# THS7002CPWP_Schematic.net
KiCad netlist of a schematic drawn in Altium Designer
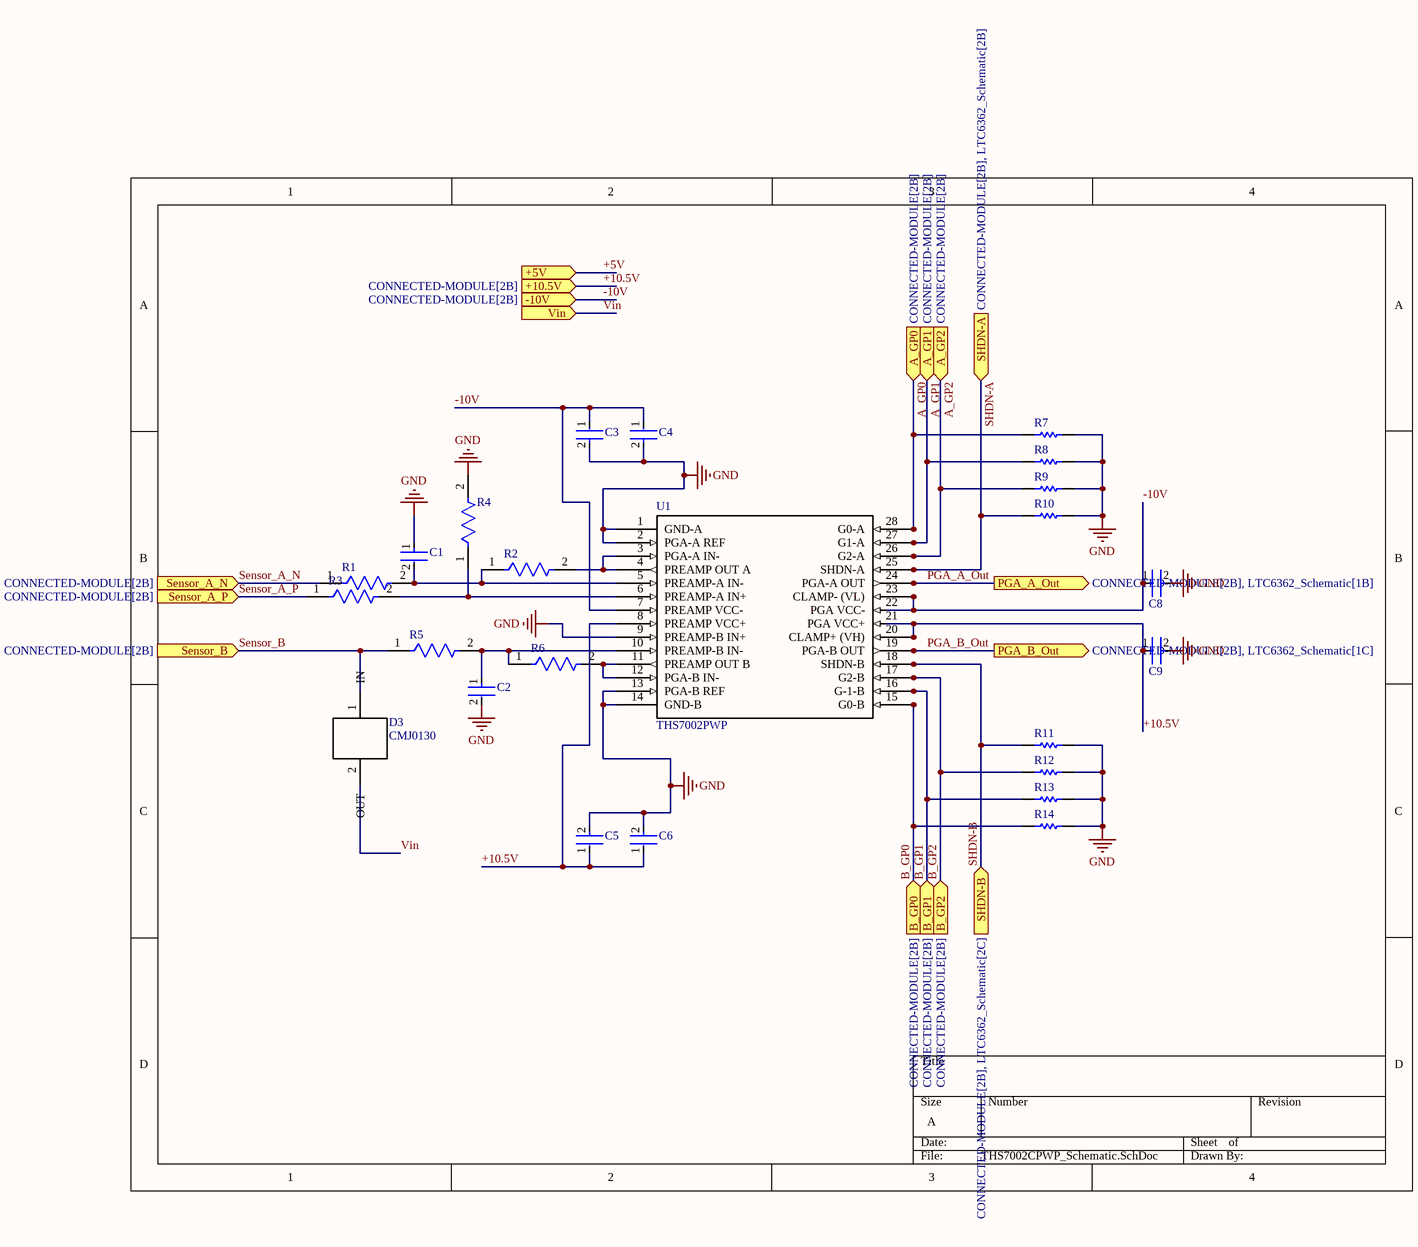
[diagram p0: THS7002CPWP_Schematic.SchDoc]

(export (version "E")
  (design (tool "Eeschema 10.0.6"))
  (components
    (comp (ref "C1")
      (value "GRM1557U1A302JA01D")
      (footprint "FP-GRM155-0_05-IPC_B")
      (description "Chip Multilayer Ceramic Capacitors for General Purpose, 0402, 3000pF, U2J, -750ppm/°C, 5%, 10V")
      (fields (field (name "TOLERANCE") "5%"))
      (libsource (lib "Altium Content Vault") (part "02cd4be3c70576c341d710602a673aa"))
    )
    (comp (ref "C2")
      (value "C0603C622J5GACTU")
      (footprint "FP-C0603C-CF-MFG")
      (fields
        (field (name "MANUFACTURER") "KEMET")
        (field (name "OCTOPART") "https://octopart.com/c0603c622j5gactu-kemet-19757383")
        (field (name "TOLERANCE") "0.05")
      )
      (libsource (lib "Altium Content Vault") (part "b4654b650e69147ec39a6b967a45e02"))
    )
    (comp (ref "C3")
      (value "GRM155R71C104KA88D")
      (footprint "FP-GRM15-MFG")
      (description "CAP CER 0.1UF 16V X7R 0402")
      (fields
        (field (name "TOLERANCE") "10%")
        (field (name "OCTOPART") "https://octopart.com/grm155r71c104ka88d-murata-196880")
      )
      (libsource (lib "Altium Content Vault") (part "236180d848d6139a670b325ea6854c9"))
    )
    (comp (ref "C4")
      (value "C1608X5R1A685K080AC")
      (footprint "FP-C1608-080-0_1-IPC_B")
      (description "Multilayer Ceramic Capacitors 6.8μF ±10% 10V X5R SMD 0603")
      (fields (field (name "TOLERANCE") "10%"))
      (libsource (lib "Altium Content Vault") (part "236180d848d6139a670b325ea6854c9"))
    )
    (comp (ref "C5")
      (value "GRM155R71C104KA88D")
      (footprint "FP-GRM15-MFG")
      (description "CAP CER 0.1UF 16V X7R 0402")
      (fields
        (field (name "TOLERANCE") "10%")
        (field (name "OCTOPART") "https://octopart.com/grm155r71c104ka88d-murata-196880")
      )
      (libsource (lib "Altium Content Vault") (part "236180d848d6139a670b325ea6854c9"))
    )
    (comp (ref "C6")
      (value "C1608X5R1A685K080AC")
      (footprint "FP-C1608-080-0_1-IPC_B")
      (description "Multilayer Ceramic Capacitors 6.8μF ±10% 10V X5R SMD 0603")
      (fields (field (name "TOLERANCE") "10%"))
      (libsource (lib "Altium Content Vault") (part "236180d848d6139a670b325ea6854c9"))
    )
    (comp (ref "C8")
      (value "GRM155R71C104KA88D")
      (footprint "FP-GRM15-MFG")
      (description "CAP CER 0.1UF 16V X7R 0402")
      (fields
        (field (name "TOLERANCE") "10%")
        (field (name "OCTOPART") "https://octopart.com/grm155r71c104ka88d-murata-196880")
      )
      (libsource (lib "Altium Content Vault") (part "236180d848d6139a670b325ea6854c9"))
    )
    (comp (ref "C9")
      (value "GRM155R71C104KA88D")
      (footprint "FP-GRM15-MFG")
      (description "CAP CER 0.1UF 16V X7R 0402")
      (fields
        (field (name "TOLERANCE") "10%")
        (field (name "OCTOPART") "https://octopart.com/grm155r71c104ka88d-murata-196880")
      )
      (libsource (lib "Altium Content Vault") (part "236180d848d6139a670b325ea6854c9"))
    )
    (comp (ref "D3")
      (value "CMJ0130")
      (footprint "CMJ2000_Footprint")
      (description "CMJ2000: DIODE CUR REG 100V 2.32MA 500MW; CMJ0130 DIODE CUR REG 100V 0.5mA 500MW")
      (libsource (lib "CMJ2000_Schematic") (part "CMJ2000/0130"))
    )
    (comp (ref "R1")
      (value "CRCW0402499RFKED")
      (footprint "FP-CRCW0402-e3-IPC_A")
      (description "RES Thick Film, 499Ω, 1%, 0.063W, 100ppm/°C, 0402")
      (fields (field (name "TOLERANCE") "1%"))
      (libsource (lib "Altium Content Vault") (part "1029c3af85768c4190bb7ad29bc67b5"))
    )
    (comp (ref "R2")
      (value "CRCW0402499RFKED")
      (footprint "FP-CRCW0402-e3-IPC_A")
      (description "RES Thick Film, 499Ω, 1%, 0.063W, 100ppm/°C, 0402")
      (fields (field (name "TOLERANCE") "1%"))
      (libsource (lib "Altium Content Vault") (part "1029c3af85768c4190bb7ad29bc67b5"))
    )
    (comp (ref "R3")
      (value "CRCW0402499RFKED")
      (footprint "FP-CRCW0402-e3-IPC_A")
      (description "RES Thick Film, 499Ω, 1%, 0.063W, 100ppm/°C, 0402")
      (fields (field (name "TOLERANCE") "1%"))
      (libsource (lib "Altium Content Vault") (part "1029c3af85768c4190bb7ad29bc67b5"))
    )
    (comp (ref "R4")
      (value "CRCW0402499RFKED")
      (footprint "FP-CRCW0402-e3-IPC_A")
      (description "RES Thick Film, 499Ω, 1%, 0.063W, 100ppm/°C, 0402")
      (fields (field (name "TOLERANCE") "1%"))
      (libsource (lib "Altium Content Vault") (part "1029c3af85768c4190bb7ad29bc67b5"))
    )
    (comp (ref "R5")
      (value "CRCW0402499RFKED")
      (footprint "FP-CRCW0402-e3-IPC_A")
      (description "RES Thick Film, 499Ω, 1%, 0.063W, 100ppm/°C, 0402")
      (fields (field (name "TOLERANCE") "1%"))
      (libsource (lib "Altium Content Vault") (part "1029c3af85768c4190bb7ad29bc67b5"))
    )
    (comp (ref "R6")
      (value "CRCW0402499RFKED")
      (footprint "FP-CRCW0402-e3-IPC_A")
      (description "RES Thick Film, 499Ω, 1%, 0.063W, 100ppm/°C, 0402")
      (fields (field (name "TOLERANCE") "1%"))
      (libsource (lib "Altium Content Vault") (part "1029c3af85768c4190bb7ad29bc67b5"))
    )
    (comp (ref "R7")
      (value "ERJ-2RKF3301X")
      (footprint "RESC1005X40X25ML05T05")
      (description "Chip Resistor, 3.3 KOhm, +/- 1%, 0.1 W, -55 to 155 degC, 0402 (1005 Metric), RoHS, Tape and Reel")
      (fields (field (name "MANUFACTURER") "Panasonic") (field (name "TOLERANCE") "1%"))
      (libsource (lib "Altium Content Vault") (part "RES-2"))
    )
    (comp (ref "R8")
      (value "ERJ-2RKF3301X")
      (footprint "RESC1005X40X25ML05T05")
      (description "Chip Resistor, 3.3 KOhm, +/- 1%, 0.1 W, -55 to 155 degC, 0402 (1005 Metric), RoHS, Tape and Reel")
      (fields (field (name "MANUFACTURER") "Panasonic") (field (name "TOLERANCE") "1%"))
      (libsource (lib "Altium Content Vault") (part "RES-2"))
    )
    (comp (ref "R9")
      (value "ERJ-2RKF3301X")
      (footprint "RESC1005X40X25ML05T05")
      (description "Chip Resistor, 3.3 KOhm, +/- 1%, 0.1 W, -55 to 155 degC, 0402 (1005 Metric), RoHS, Tape and Reel")
      (fields (field (name "MANUFACTURER") "Panasonic") (field (name "TOLERANCE") "1%"))
      (libsource (lib "Altium Content Vault") (part "RES-2"))
    )
    (comp (ref "R10")
      (value "ERJ-2RKF3301X")
      (footprint "RESC1005X40X25ML05T05")
      (description "Chip Resistor, 3.3 KOhm, +/- 1%, 0.1 W, -55 to 155 degC, 0402 (1005 Metric), RoHS, Tape and Reel")
      (fields (field (name "MANUFACTURER") "Panasonic") (field (name "TOLERANCE") "1%"))
      (libsource (lib "Altium Content Vault") (part "RES-2"))
    )
    (comp (ref "R11")
      (value "ERJ-2RKF3301X")
      (footprint "RESC1005X40X25ML05T05")
      (description "Chip Resistor, 3.3 KOhm, +/- 1%, 0.1 W, -55 to 155 degC, 0402 (1005 Metric), RoHS, Tape and Reel")
      (fields (field (name "MANUFACTURER") "Panasonic") (field (name "TOLERANCE") "1%"))
      (libsource (lib "Altium Content Vault") (part "RES-2"))
    )
    (comp (ref "R12")
      (value "ERJ-2RKF3301X")
      (footprint "RESC1005X40X25ML05T05")
      (description "Chip Resistor, 3.3 KOhm, +/- 1%, 0.1 W, -55 to 155 degC, 0402 (1005 Metric), RoHS, Tape and Reel")
      (fields (field (name "MANUFACTURER") "Panasonic") (field (name "TOLERANCE") "1%"))
      (libsource (lib "Altium Content Vault") (part "RES-2"))
    )
    (comp (ref "R13")
      (value "ERJ-2RKF3301X")
      (footprint "RESC1005X40X25ML05T05")
      (description "Chip Resistor, 3.3 KOhm, +/- 1%, 0.1 W, -55 to 155 degC, 0402 (1005 Metric), RoHS, Tape and Reel")
      (fields (field (name "MANUFACTURER") "Panasonic") (field (name "TOLERANCE") "1%"))
      (libsource (lib "Altium Content Vault") (part "RES-2"))
    )
    (comp (ref "R14")
      (value "ERJ-2RKF3301X")
      (footprint "RESC1005X40X25ML05T05")
      (description "Chip Resistor, 3.3 KOhm, +/- 1%, 0.1 W, -55 to 155 degC, 0402 (1005 Metric), RoHS, Tape and Reel")
      (fields (field (name "MANUFACTURER") "Panasonic") (field (name "TOLERANCE") "1%"))
      (libsource (lib "Altium Content Vault") (part "RES-2"))
    )
    (comp (ref "U1")
      (value "THS7002PWP")
      (footprint "PWP0028E_N")
      (libsource (lib "THS7002_New_Schematic") (part "Component_1"))
    )
  )
  (nets
    (net (code "2") (name "/+10.5V") (class "Default")
      (node (ref "C5") (pin "1") (pinfunction "1_1") (pintype "passive"))
      (node (ref "C6") (pin "1") (pinfunction "1_1") (pintype "passive"))
      (node (ref "C9") (pin "1") (pinfunction "1_1") (pintype "passive"))
      (node (ref "U1") (pin "20") (pinfunction "CLAMP+_(VH)_20") (pintype "input"))
      (node (ref "U1") (pin "21") (pinfunction "PGA_VCC+_21") (pintype "input"))
      (node (ref "U1") (pin "8") (pinfunction "PREAMP_VCC+_8") (pintype "input"))
    )
    (net (code "3") (name "/-10V") (class "Default")
      (node (ref "C3") (pin "1") (pinfunction "1_1") (pintype "passive"))
      (node (ref "C4") (pin "1") (pinfunction "1_1") (pintype "passive"))
      (node (ref "C8") (pin "1") (pinfunction "1_1") (pintype "passive"))
      (node (ref "U1") (pin "22") (pinfunction "PGA_VCC-_22") (pintype "input"))
      (node (ref "U1") (pin "23") (pinfunction "CLAMP-_(VL)_23") (pintype "input"))
      (node (ref "U1") (pin "7") (pinfunction "PREAMP_VCC-_7") (pintype "input"))
    )
    (net (code "4") (name "/A_GP0") (class "Default")
      (node (ref "R7") (pin "1") (pinfunction "1_1") (pintype "passive"))
      (node (ref "U1") (pin "28") (pinfunction "G0-A_28") (pintype "input"))
    )
    (net (code "5") (name "/A_GP1") (class "Default")
      (node (ref "R8") (pin "1") (pinfunction "1_1") (pintype "passive"))
      (node (ref "U1") (pin "27") (pinfunction "G1-A_27") (pintype "input"))
    )
    (net (code "6") (name "/A_GP2") (class "Default")
      (node (ref "R9") (pin "1") (pinfunction "1_1") (pintype "passive"))
      (node (ref "U1") (pin "26") (pinfunction "G2-A_26") (pintype "input"))
    )
    (net (code "7") (name "/B_GP0") (class "Default")
      (node (ref "R14") (pin "1") (pinfunction "1_1") (pintype "passive"))
      (node (ref "U1") (pin "15") (pinfunction "G0-B_15") (pintype "input"))
    )
    (net (code "8") (name "/B_GP1") (class "Default")
      (node (ref "R13") (pin "1") (pinfunction "1_1") (pintype "passive"))
      (node (ref "U1") (pin "16") (pinfunction "G-1-B_16") (pintype "input"))
    )
    (net (code "9") (name "/B_GP2") (class "Default")
      (node (ref "R12") (pin "1") (pinfunction "1_1") (pintype "passive"))
      (node (ref "U1") (pin "17") (pinfunction "G2-B_17") (pintype "input"))
    )
    (net (code "10") (name "/PGA_A_Out") (class "Default")
      (node (ref "U1") (pin "24") (pinfunction "PGA-A_OUT_24") (pintype "output"))
    )
    (net (code "11") (name "/PGA_B_Out") (class "Default")
      (node (ref "U1") (pin "19") (pinfunction "PGA-B_OUT_19") (pintype "output"))
    )
    (net (code "12") (name "/SHDN-A") (class "Default")
      (node (ref "R10") (pin "1") (pinfunction "1_1") (pintype "passive"))
      (node (ref "U1") (pin "25") (pinfunction "SHDN-A_25") (pintype "input"))
    )
    (net (code "13") (name "/SHDN-B") (class "Default")
      (node (ref "R11") (pin "1") (pinfunction "1_1") (pintype "passive"))
      (node (ref "U1") (pin "18") (pinfunction "SHDN-B_18") (pintype "input"))
    )
    (net (code "14") (name "/Sensor_A_N") (class "Default")
      (node (ref "R1") (pin "1") (pinfunction "1_1") (pintype "passive"))
    )
    (net (code "15") (name "/Sensor_A_P") (class "Default")
      (node (ref "R3") (pin "1") (pinfunction "1_1") (pintype "passive"))
    )
    (net (code "16") (name "/Sensor_B") (class "Default")
      (node (ref "R5") (pin "1") (pinfunction "1_1") (pintype "passive"))
    )
    (net (code "18") (name "GND") (class "Default")
      (node (ref "C1") (pin "1") (pinfunction "1_1") (pintype "passive"))
      (node (ref "C2") (pin "2") (pinfunction "2_2") (pintype "passive"))
      (node (ref "C3") (pin "2") (pinfunction "2_2") (pintype "passive"))
      (node (ref "C4") (pin "2") (pinfunction "2_2") (pintype "passive"))
      (node (ref "C5") (pin "2") (pinfunction "2_2") (pintype "passive"))
      (node (ref "C6") (pin "2") (pinfunction "2_2") (pintype "passive"))
      (node (ref "C8") (pin "2") (pinfunction "2_2") (pintype "passive"))
      (node (ref "C9") (pin "2") (pinfunction "2_2") (pintype "passive"))
      (node (ref "R10") (pin "2") (pinfunction "2_2") (pintype "passive"))
      (node (ref "R11") (pin "2") (pinfunction "2_2") (pintype "passive"))
      (node (ref "R12") (pin "2") (pinfunction "2_2") (pintype "passive"))
      (node (ref "R13") (pin "2") (pinfunction "2_2") (pintype "passive"))
      (node (ref "R14") (pin "2") (pinfunction "2_2") (pintype "passive"))
      (node (ref "R4") (pin "2") (pinfunction "2_2") (pintype "passive"))
      (node (ref "R7") (pin "2") (pinfunction "2_2") (pintype "passive"))
      (node (ref "R8") (pin "2") (pinfunction "2_2") (pintype "passive"))
      (node (ref "R9") (pin "2") (pinfunction "2_2") (pintype "passive"))
      (node (ref "U1") (pin "1") (pinfunction "GND-A_1") (pintype "passive"))
      (node (ref "U1") (pin "13") (pinfunction "PGA-B_REF_13") (pintype "input"))
      (node (ref "U1") (pin "14") (pinfunction "GND-B_14") (pintype "passive"))
      (node (ref "U1") (pin "2") (pinfunction "PGA-A_REF_2") (pintype "input"))
      (node (ref "U1") (pin "9") (pinfunction "PREAMP-B_IN+_9") (pintype "input"))
    )
    (net (code "19") (name "Net-(U1-PGA-A_IN-)") (class "Default")
      (node (ref "R2") (pin "2") (pinfunction "2_2") (pintype "passive"))
      (node (ref "U1") (pin "3") (pinfunction "PGA-A_IN-_3") (pintype "input"))
      (node (ref "U1") (pin "4") (pinfunction "PREAMP_OUT_A_4") (pintype "output"))
    )
    (net (code "20") (name "Net-(U1-PGA-B_IN-)") (class "Default")
      (node (ref "R6") (pin "2") (pinfunction "2_2") (pintype "passive"))
      (node (ref "U1") (pin "11") (pinfunction "PREAMP_OUT_B_11") (pintype "output"))
      (node (ref "U1") (pin "12") (pinfunction "PGA-B_IN-_12") (pintype "input"))
    )
    (net (code "21") (name "Net-(U1-PREAMP-A_IN+)") (class "Default")
      (node (ref "R3") (pin "2") (pinfunction "2_2") (pintype "passive"))
      (node (ref "R4") (pin "1") (pinfunction "1_1") (pintype "passive"))
      (node (ref "U1") (pin "6") (pinfunction "PREAMP-A_IN+_6") (pintype "input"))
    )
    (net (code "22") (name "Net-(U1-PREAMP-A_IN-)") (class "Default")
      (node (ref "C1") (pin "2") (pinfunction "2_2") (pintype "passive"))
      (node (ref "R1") (pin "2") (pinfunction "2_2") (pintype "passive"))
      (node (ref "R2") (pin "1") (pinfunction "1_1") (pintype "passive"))
      (node (ref "U1") (pin "5") (pinfunction "PREAMP-A_IN-_5") (pintype "input"))
    )
    (net (code "23") (name "Net-(U1-PREAMP-B_IN-)") (class "Default")
      (node (ref "C2") (pin "1") (pinfunction "1_1") (pintype "passive"))
      (node (ref "R5") (pin "2") (pinfunction "2_2") (pintype "passive"))
      (node (ref "R6") (pin "1") (pinfunction "1_1") (pintype "passive"))
      (node (ref "U1") (pin "10") (pinfunction "PREAMP-B_IN-_10") (pintype "input"))
    )
    (net (code "24") (name "unconnected-(D3-IN-Pad1)") (class "Default")
      (node (ref "D3") (pin "1") (pinfunction "IN_1") (pintype "passive"))
    )
    (net (code "25") (name "unconnected-(D3-OUT-Pad2)") (class "Default")
      (node (ref "D3") (pin "2") (pinfunction "OUT_2") (pintype "passive"))
    )
  )
)
